# LED_String_NF2L757GT-F1.net
KiCad netlist of a schematic drawn in Altium Designer
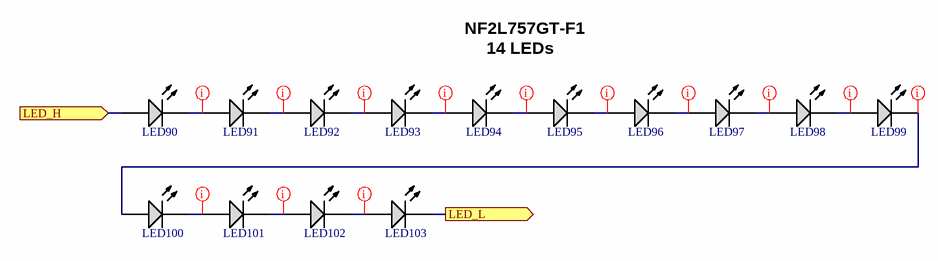
[diagram p0: LED_String_NF2L757GT-F1.SchDoc]

(export (version "E")
  (design (tool "Eeschema 10.0.6"))
  (components
    (comp (ref "LED90")
      (value "NF2L757GT-F1")
      (footprint "NF2W757GT-F1")
      (description "SMD LED White 2,76 V, 31,2 lm 3030 (1212)")
      (fields
        (field (name "MANUFACTURER") "Nichia")
        (field (name "MANUFACTURER PART NUMBER") "NF2L757GT-F1 Optisolis")
      )
      (libsource (lib "ETHZ Vault") (part "LED White"))
    )
    (comp (ref "LED91")
      (value "NF2L757GT-F1")
      (footprint "NF2W757GT-F1")
      (description "SMD LED White 2,76 V, 31,2 lm 3030 (1212)")
      (fields
        (field (name "MANUFACTURER") "Nichia")
        (field (name "MANUFACTURER PART NUMBER") "NF2L757GT-F1 Optisolis")
      )
      (libsource (lib "ETHZ Vault") (part "LED White"))
    )
    (comp (ref "LED92")
      (value "NF2L757GT-F1")
      (footprint "NF2W757GT-F1")
      (description "SMD LED White 2,76 V, 31,2 lm 3030 (1212)")
      (fields
        (field (name "MANUFACTURER") "Nichia")
        (field (name "MANUFACTURER PART NUMBER") "NF2L757GT-F1 Optisolis")
      )
      (libsource (lib "ETHZ Vault") (part "LED White"))
    )
    (comp (ref "LED93")
      (value "NF2L757GT-F1")
      (footprint "NF2W757GT-F1")
      (description "SMD LED White 2,76 V, 31,2 lm 3030 (1212)")
      (fields
        (field (name "MANUFACTURER") "Nichia")
        (field (name "MANUFACTURER PART NUMBER") "NF2L757GT-F1 Optisolis")
      )
      (libsource (lib "ETHZ Vault") (part "LED White"))
    )
    (comp (ref "LED94")
      (value "NF2L757GT-F1")
      (footprint "NF2W757GT-F1")
      (description "SMD LED White 2,76 V, 31,2 lm 3030 (1212)")
      (fields
        (field (name "MANUFACTURER") "Nichia")
        (field (name "MANUFACTURER PART NUMBER") "NF2L757GT-F1 Optisolis")
      )
      (libsource (lib "ETHZ Vault") (part "LED White"))
    )
    (comp (ref "LED95")
      (value "NF2L757GT-F1")
      (footprint "NF2W757GT-F1")
      (description "SMD LED White 2,76 V, 31,2 lm 3030 (1212)")
      (fields
        (field (name "MANUFACTURER") "Nichia")
        (field (name "MANUFACTURER PART NUMBER") "NF2L757GT-F1 Optisolis")
      )
      (libsource (lib "ETHZ Vault") (part "LED White"))
    )
    (comp (ref "LED96")
      (value "NF2L757GT-F1")
      (footprint "NF2W757GT-F1")
      (description "SMD LED White 2,76 V, 31,2 lm 3030 (1212)")
      (fields
        (field (name "MANUFACTURER") "Nichia")
        (field (name "MANUFACTURER PART NUMBER") "NF2L757GT-F1 Optisolis")
      )
      (libsource (lib "ETHZ Vault") (part "LED White"))
    )
    (comp (ref "LED97")
      (value "NF2L757GT-F1")
      (footprint "NF2W757GT-F1")
      (description "SMD LED White 2,76 V, 31,2 lm 3030 (1212)")
      (fields
        (field (name "MANUFACTURER") "Nichia")
        (field (name "MANUFACTURER PART NUMBER") "NF2L757GT-F1 Optisolis")
      )
      (libsource (lib "ETHZ Vault") (part "LED White"))
    )
    (comp (ref "LED98")
      (value "NF2L757GT-F1")
      (footprint "NF2W757GT-F1")
      (description "SMD LED White 2,76 V, 31,2 lm 3030 (1212)")
      (fields
        (field (name "MANUFACTURER") "Nichia")
        (field (name "MANUFACTURER PART NUMBER") "NF2L757GT-F1 Optisolis")
      )
      (libsource (lib "ETHZ Vault") (part "LED White"))
    )
    (comp (ref "LED99")
      (value "NF2L757GT-F1")
      (footprint "NF2W757GT-F1")
      (description "SMD LED White 2,76 V, 31,2 lm 3030 (1212)")
      (fields
        (field (name "MANUFACTURER") "Nichia")
        (field (name "MANUFACTURER PART NUMBER") "NF2L757GT-F1 Optisolis")
      )
      (libsource (lib "ETHZ Vault") (part "LED White"))
    )
    (comp (ref "LED100")
      (value "NF2L757GT-F1")
      (footprint "NF2W757GT-F1")
      (description "SMD LED White 2,76 V, 31,2 lm 3030 (1212)")
      (fields
        (field (name "MANUFACTURER") "Nichia")
        (field (name "MANUFACTURER PART NUMBER") "NF2L757GT-F1 Optisolis")
      )
      (libsource (lib "ETHZ Vault") (part "LED White"))
    )
    (comp (ref "LED101")
      (value "NF2L757GT-F1")
      (footprint "NF2W757GT-F1")
      (description "SMD LED White 2,76 V, 31,2 lm 3030 (1212)")
      (fields
        (field (name "MANUFACTURER") "Nichia")
        (field (name "MANUFACTURER PART NUMBER") "NF2L757GT-F1 Optisolis")
      )
      (libsource (lib "ETHZ Vault") (part "LED White"))
    )
    (comp (ref "LED102")
      (value "NF2L757GT-F1")
      (footprint "NF2W757GT-F1")
      (description "SMD LED White 2,76 V, 31,2 lm 3030 (1212)")
      (fields
        (field (name "MANUFACTURER") "Nichia")
        (field (name "MANUFACTURER PART NUMBER") "NF2L757GT-F1 Optisolis")
      )
      (libsource (lib "ETHZ Vault") (part "LED White"))
    )
    (comp (ref "LED103")
      (value "NF2L757GT-F1")
      (footprint "NF2W757GT-F1")
      (description "SMD LED White 2,76 V, 31,2 lm 3030 (1212)")
      (fields
        (field (name "MANUFACTURER") "Nichia")
        (field (name "MANUFACTURER PART NUMBER") "NF2L757GT-F1 Optisolis")
      )
      (libsource (lib "ETHZ Vault") (part "LED White"))
    )
  )
  (nets
    (net (code "1") (name "/LED_H") (class "Default")
      (node (ref "LED90") (pin "2") (pinfunction "A_2") (pintype "passive"))
    )
    (net (code "2") (name "/LED_L") (class "Default")
      (node (ref "LED103") (pin "1") (pinfunction "K_1") (pintype "passive"))
    )
    (net (code "3") (name "Net-(LED90-K)") (class "Default")
      (node (ref "LED90") (pin "1") (pinfunction "K_1") (pintype "passive"))
      (node (ref "LED91") (pin "2") (pinfunction "A_2") (pintype "passive"))
    )
    (net (code "4") (name "Net-(LED91-K)") (class "Default")
      (node (ref "LED91") (pin "1") (pinfunction "K_1") (pintype "passive"))
      (node (ref "LED92") (pin "2") (pinfunction "A_2") (pintype "passive"))
    )
    (net (code "5") (name "Net-(LED92-K)") (class "Default")
      (node (ref "LED92") (pin "1") (pinfunction "K_1") (pintype "passive"))
      (node (ref "LED93") (pin "2") (pinfunction "A_2") (pintype "passive"))
    )
    (net (code "6") (name "Net-(LED93-K)") (class "Default")
      (node (ref "LED93") (pin "1") (pinfunction "K_1") (pintype "passive"))
      (node (ref "LED94") (pin "2") (pinfunction "A_2") (pintype "passive"))
    )
    (net (code "7") (name "Net-(LED94-K)") (class "Default")
      (node (ref "LED94") (pin "1") (pinfunction "K_1") (pintype "passive"))
      (node (ref "LED95") (pin "2") (pinfunction "A_2") (pintype "passive"))
    )
    (net (code "8") (name "Net-(LED95-K)") (class "Default")
      (node (ref "LED95") (pin "1") (pinfunction "K_1") (pintype "passive"))
      (node (ref "LED96") (pin "2") (pinfunction "A_2") (pintype "passive"))
    )
    (net (code "9") (name "Net-(LED96-K)") (class "Default")
      (node (ref "LED96") (pin "1") (pinfunction "K_1") (pintype "passive"))
      (node (ref "LED97") (pin "2") (pinfunction "A_2") (pintype "passive"))
    )
    (net (code "10") (name "Net-(LED97-K)") (class "Default")
      (node (ref "LED97") (pin "1") (pinfunction "K_1") (pintype "passive"))
      (node (ref "LED98") (pin "2") (pinfunction "A_2") (pintype "passive"))
    )
    (net (code "11") (name "Net-(LED98-K)") (class "Default")
      (node (ref "LED98") (pin "1") (pinfunction "K_1") (pintype "passive"))
      (node (ref "LED99") (pin "2") (pinfunction "A_2") (pintype "passive"))
    )
    (net (code "12") (name "Net-(LED100-A)") (class "Default")
      (node (ref "LED100") (pin "2") (pinfunction "A_2") (pintype "passive"))
      (node (ref "LED99") (pin "1") (pinfunction "K_1") (pintype "passive"))
    )
    (net (code "13") (name "Net-(LED100-K)") (class "Default")
      (node (ref "LED100") (pin "1") (pinfunction "K_1") (pintype "passive"))
      (node (ref "LED101") (pin "2") (pinfunction "A_2") (pintype "passive"))
    )
    (net (code "14") (name "Net-(LED101-K)") (class "Default")
      (node (ref "LED101") (pin "1") (pinfunction "K_1") (pintype "passive"))
      (node (ref "LED102") (pin "2") (pinfunction "A_2") (pintype "passive"))
    )
    (net (code "15") (name "Net-(LED102-K)") (class "Default")
      (node (ref "LED102") (pin "1") (pinfunction "K_1") (pintype "passive"))
      (node (ref "LED103") (pin "2") (pinfunction "A_2") (pintype "passive"))
    )
  )
)
